# tec_controller_v2.net
KiCad netlist of a schematic drawn in EAGLE
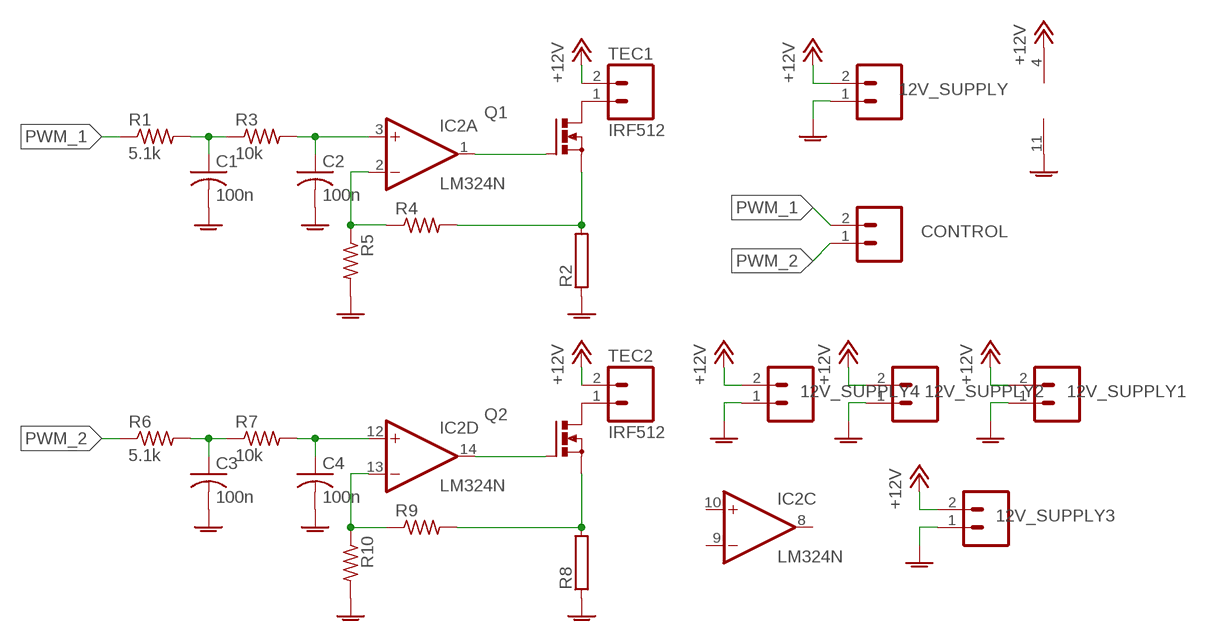
[diagram p0: schematic, sheet 1]

(export (version "E")
  (design (tool "Eeschema 10.0.6"))
  (components
    (comp (ref "12V_SUPPLY")
      (value "M02LOCK_LONGPADS")
      (footprint "eagle-import:1X02_LOCK_LONGPADS")
      (libsource (lib "eagle-import") (part "M02LOCK_LONGPADS"))
    )
    (comp (ref "12V_SUPPLY1")
      (value "M02LOCK_LONGPADS")
      (footprint "eagle-import:1X02_LOCK_LONGPADS")
      (libsource (lib "eagle-import") (part "M02LOCK_LONGPADS"))
    )
    (comp (ref "12V_SUPPLY2")
      (value "M02LOCK_LONGPADS")
      (footprint "eagle-import:1X02_LOCK_LONGPADS")
      (libsource (lib "eagle-import") (part "M02LOCK_LONGPADS"))
    )
    (comp (ref "12V_SUPPLY3")
      (value "M02LOCK_LONGPADS")
      (footprint "eagle-import:1X02_LOCK_LONGPADS")
      (libsource (lib "eagle-import") (part "M02LOCK_LONGPADS"))
    )
    (comp (ref "12V_SUPPLY4")
      (value "M02LOCK_LONGPADS")
      (footprint "eagle-import:1X02_LOCK_LONGPADS")
      (libsource (lib "eagle-import") (part "M02LOCK_LONGPADS"))
    )
    (comp (ref "C1")
      (value "100n")
      (footprint "eagle-import:C0805")
      (libsource (lib "eagle-import") (part "C-USC0805"))
    )
    (comp (ref "C2")
      (value "100n")
      (footprint "eagle-import:C0805")
      (libsource (lib "eagle-import") (part "C-USC0805"))
    )
    (comp (ref "C3")
      (value "100n")
      (footprint "eagle-import:C0805")
      (libsource (lib "eagle-import") (part "C-USC0805"))
    )
    (comp (ref "C4")
      (value "100n")
      (footprint "eagle-import:C0805")
      (libsource (lib "eagle-import") (part "C-USC0805"))
    )
    (comp (ref "CONTROL")
      (value "M02LOCK_LONGPADS")
      (footprint "eagle-import:1X02_LOCK_LONGPADS")
      (libsource (lib "eagle-import") (part "M02LOCK_LONGPADS"))
    )
    (comp (ref "IC2")
      (value "LM324N")
      (footprint "eagle-import:DIL14")
      (libsource (lib "eagle-import") (part "LM324N"))
    )
    (comp (ref "Q1")
      (value "IRF512")
      (footprint "eagle-import:TO220BV")
      (libsource (lib "eagle-import") (part "IRF512"))
    )
    (comp (ref "Q2")
      (value "IRF512")
      (footprint "eagle-import:TO220BV")
      (libsource (lib "eagle-import") (part "IRF512"))
    )
    (comp (ref "R1")
      (value "5.1k")
      (footprint "eagle-import:M0805")
      (libsource (lib "eagle-import") (part "R-US_M0805"))
    )
    (comp (ref "R2")
      (value "RAC10")
      (footprint "eagle-import:AC10")
      (libsource (lib "eagle-import") (part "RAC10"))
    )
    (comp (ref "R3")
      (value "10k")
      (footprint "eagle-import:M0805")
      (libsource (lib "eagle-import") (part "R-US_M0805"))
    )
    (comp (ref "R4")
      (value "R-US_M0805")
      (footprint "eagle-import:M0805")
      (libsource (lib "eagle-import") (part "R-US_M0805"))
    )
    (comp (ref "R5")
      (value "R-US_M0805")
      (footprint "eagle-import:M0805")
      (libsource (lib "eagle-import") (part "R-US_M0805"))
    )
    (comp (ref "R6")
      (value "5.1k")
      (footprint "eagle-import:M0805")
      (libsource (lib "eagle-import") (part "R-US_M0805"))
    )
    (comp (ref "R7")
      (value "10k")
      (footprint "eagle-import:M0805")
      (libsource (lib "eagle-import") (part "R-US_M0805"))
    )
    (comp (ref "R8")
      (value "RAC10")
      (footprint "eagle-import:AC10")
      (libsource (lib "eagle-import") (part "RAC10"))
    )
    (comp (ref "R9")
      (value "R-US_M0805")
      (footprint "eagle-import:M0805")
      (libsource (lib "eagle-import") (part "R-US_M0805"))
    )
    (comp (ref "R10")
      (value "R-US_M0805")
      (footprint "eagle-import:M0805")
      (libsource (lib "eagle-import") (part "R-US_M0805"))
    )
    (comp (ref "TEC1")
      (value "M02LOCK_LONGPADS")
      (footprint "eagle-import:1X02_LOCK_LONGPADS")
      (libsource (lib "eagle-import") (part "M02LOCK_LONGPADS"))
    )
    (comp (ref "TEC2")
      (value "M02LOCK_LONGPADS")
      (footprint "eagle-import:1X02_LOCK_LONGPADS")
      (libsource (lib "eagle-import") (part "M02LOCK_LONGPADS"))
    )
  )
  (nets
    (net (code "1") (name "+12V") (class "Default")
      (node (ref "12V_SUPPLY") (pin "2") (pinfunction "2_2") (pintype "passive"))
      (node (ref "12V_SUPPLY1") (pin "2") (pinfunction "2_2") (pintype "passive"))
      (node (ref "12V_SUPPLY2") (pin "2") (pinfunction "2_2") (pintype "passive"))
      (node (ref "12V_SUPPLY3") (pin "2") (pinfunction "2_2") (pintype "passive"))
      (node (ref "12V_SUPPLY4") (pin "2") (pinfunction "2_2") (pintype "passive"))
      (node (ref "IC2") (pin "4") (pinfunction "V+_4") (pintype "power_in"))
      (node (ref "TEC1") (pin "2") (pinfunction "2_2") (pintype "passive"))
      (node (ref "TEC2") (pin "2") (pinfunction "2_2") (pintype "passive"))
    )
    (net (code "2") (name "GNDA") (class "Default")
      (node (ref "12V_SUPPLY") (pin "1") (pinfunction "1_1") (pintype "passive"))
      (node (ref "12V_SUPPLY1") (pin "1") (pinfunction "1_1") (pintype "passive"))
      (node (ref "12V_SUPPLY2") (pin "1") (pinfunction "1_1") (pintype "passive"))
      (node (ref "12V_SUPPLY3") (pin "1") (pinfunction "1_1") (pintype "passive"))
      (node (ref "12V_SUPPLY4") (pin "1") (pinfunction "1_1") (pintype "passive"))
      (node (ref "C1") (pin "2") (pinfunction "2_2") (pintype "passive"))
      (node (ref "C2") (pin "2") (pinfunction "2_2") (pintype "passive"))
      (node (ref "C3") (pin "2") (pinfunction "2_2") (pintype "passive"))
      (node (ref "C4") (pin "2") (pinfunction "2_2") (pintype "passive"))
      (node (ref "IC2") (pin "11") (pinfunction "V-_11") (pintype "power_in"))
      (node (ref "R10") (pin "2") (pinfunction "2_2") (pintype "passive"))
      (node (ref "R2") (pin "1") (pinfunction "1_1") (pintype "passive"))
      (node (ref "R5") (pin "2") (pinfunction "2_2") (pintype "passive"))
      (node (ref "R8") (pin "1") (pinfunction "1_1") (pintype "passive"))
    )
    (net (code "3") (name "Net-(C1-Pad1)") (class "Default")
      (node (ref "C1") (pin "1") (pinfunction "1_1") (pintype "passive"))
      (node (ref "R1") (pin "2") (pinfunction "2_2") (pintype "passive"))
      (node (ref "R3") (pin "1") (pinfunction "1_1") (pintype "passive"))
    )
    (net (code "4") (name "Net-(C3-Pad1)") (class "Default")
      (node (ref "C3") (pin "1") (pinfunction "1_1") (pintype "passive"))
      (node (ref "R6") (pin "2") (pinfunction "2_2") (pintype "passive"))
      (node (ref "R7") (pin "1") (pinfunction "1_1") (pintype "passive"))
    )
    (net (code "5") (name "Net-(IC2A-+IN)") (class "Default")
      (node (ref "C2") (pin "1") (pinfunction "1_1") (pintype "passive"))
      (node (ref "IC2") (pin "3") (pinfunction "+IN_3") (pintype "input"))
      (node (ref "R3") (pin "2") (pinfunction "2_2") (pintype "passive"))
    )
    (net (code "6") (name "Net-(IC2A--IN)") (class "Default")
      (node (ref "IC2") (pin "2") (pinfunction "-IN_2") (pintype "input"))
      (node (ref "R4") (pin "1") (pinfunction "1_1") (pintype "passive"))
      (node (ref "R5") (pin "1") (pinfunction "1_1") (pintype "passive"))
    )
    (net (code "7") (name "Net-(IC2A-OUT)") (class "Default")
      (node (ref "IC2") (pin "1") (pinfunction "OUT_1") (pintype "output"))
      (node (ref "Q1") (pin "G") (pinfunction "G_G") (pintype "passive"))
    )
    (net (code "8") (name "Net-(IC2D-+IN)") (class "Default")
      (node (ref "C4") (pin "1") (pinfunction "1_1") (pintype "passive"))
      (node (ref "IC2") (pin "12") (pinfunction "+IN_12") (pintype "input"))
      (node (ref "R7") (pin "2") (pinfunction "2_2") (pintype "passive"))
    )
    (net (code "9") (name "Net-(IC2D--IN)") (class "Default")
      (node (ref "IC2") (pin "13") (pinfunction "-IN_13") (pintype "input"))
      (node (ref "R10") (pin "1") (pinfunction "1_1") (pintype "passive"))
      (node (ref "R9") (pin "1") (pinfunction "1_1") (pintype "passive"))
    )
    (net (code "10") (name "Net-(IC2D-OUT)") (class "Default")
      (node (ref "IC2") (pin "14") (pinfunction "OUT_14") (pintype "output"))
      (node (ref "Q2") (pin "G") (pinfunction "G_G") (pintype "passive"))
    )
    (net (code "11") (name "Net-(Q1-PadD)") (class "Default")
      (node (ref "Q1") (pin "D") (pinfunction "D_D") (pintype "passive"))
      (node (ref "TEC1") (pin "1") (pinfunction "1_1") (pintype "passive"))
    )
    (net (code "12") (name "Net-(Q1-PadS)") (class "Default")
      (node (ref "Q1") (pin "S") (pinfunction "S_S") (pintype "passive"))
      (node (ref "R2") (pin "2") (pinfunction "2_2") (pintype "passive"))
      (node (ref "R4") (pin "2") (pinfunction "2_2") (pintype "passive"))
    )
    (net (code "13") (name "Net-(Q2-PadD)") (class "Default")
      (node (ref "Q2") (pin "D") (pinfunction "D_D") (pintype "passive"))
      (node (ref "TEC2") (pin "1") (pinfunction "1_1") (pintype "passive"))
    )
    (net (code "14") (name "Net-(Q2-PadS)") (class "Default")
      (node (ref "Q2") (pin "S") (pinfunction "S_S") (pintype "passive"))
      (node (ref "R8") (pin "2") (pinfunction "2_2") (pintype "passive"))
      (node (ref "R9") (pin "2") (pinfunction "2_2") (pintype "passive"))
    )
    (net (code "15") (name "PWM_1") (class "Default")
      (node (ref "CONTROL") (pin "2") (pinfunction "2_2") (pintype "passive"))
      (node (ref "R1") (pin "1") (pinfunction "1_1") (pintype "passive"))
    )
    (net (code "16") (name "PWM_2") (class "Default")
      (node (ref "CONTROL") (pin "1") (pinfunction "1_1") (pintype "passive"))
      (node (ref "R6") (pin "1") (pinfunction "1_1") (pintype "passive"))
    )
    (net (code "17") (name "unconnected-(IC2C-+IN-Pad10)") (class "Default")
      (node (ref "IC2") (pin "10") (pinfunction "+IN_10") (pintype "input"))
    )
    (net (code "18") (name "unconnected-(IC2C--IN-Pad9)") (class "Default")
      (node (ref "IC2") (pin "9") (pinfunction "-IN_9") (pintype "input"))
    )
    (net (code "19") (name "unconnected-(IC2C-OUT-Pad8)") (class "Default")
      (node (ref "IC2") (pin "8") (pinfunction "OUT_8") (pintype "output"))
    )
  )
)
